# circuitcop.net
KiCad netlist of a schematic drawn in EAGLE
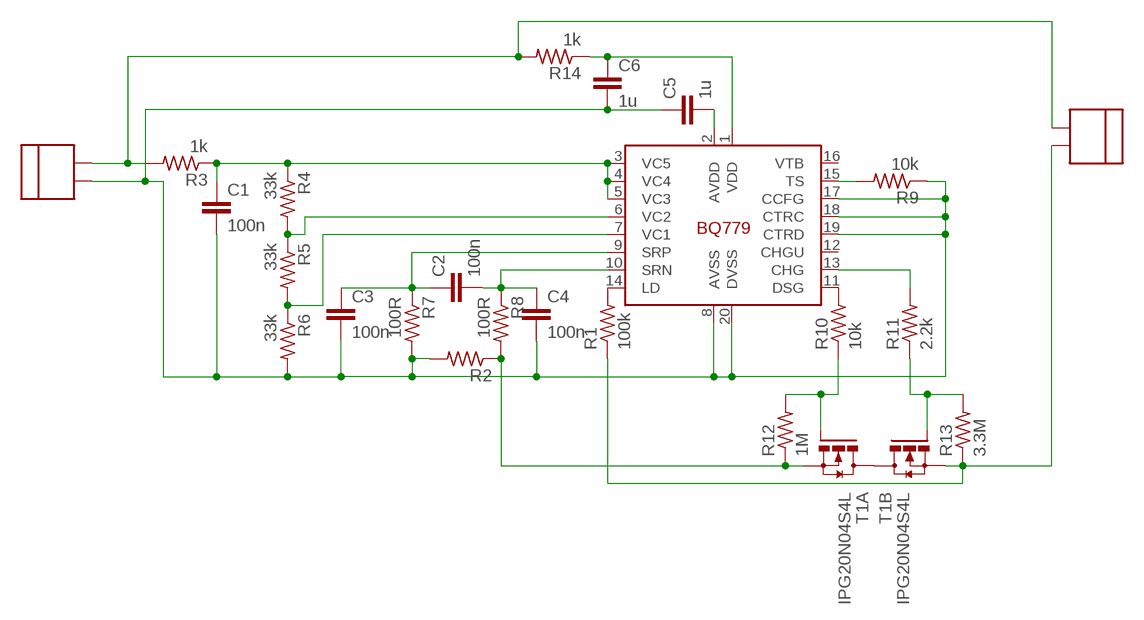
[diagram p0: schematic, sheet 1]

(export (version "E")
  (design (tool "Eeschema 10.0.6"))
  (components
    (comp (ref "C1")
      (value "100n")
      (footprint "eagle-import:C0805")
      (libsource (lib "eagle-import") (part "C-EUC0805"))
    )
    (comp (ref "C2")
      (value "100n")
      (footprint "eagle-import:C0805")
      (libsource (lib "eagle-import") (part "C-EUC0805"))
    )
    (comp (ref "C3")
      (value "100n")
      (footprint "eagle-import:C0805")
      (libsource (lib "eagle-import") (part "C-EUC0805"))
    )
    (comp (ref "C4")
      (value "100n")
      (footprint "eagle-import:C0805")
      (libsource (lib "eagle-import") (part "C-EUC0805"))
    )
    (comp (ref "C5")
      (value "1u")
      (footprint "eagle-import:C0805")
      (libsource (lib "eagle-import") (part "C-EUC0805"))
    )
    (comp (ref "C6")
      (value "1u")
      (footprint "eagle-import:C0805")
      (libsource (lib "eagle-import") (part "C-EUC0805"))
    )
    (comp (ref "R1")
      (value "100k")
      (footprint "eagle-import:R0805")
      (libsource (lib "eagle-import") (part "R-US_R0805"))
    )
    (comp (ref "R2")
      (value "R-US_R1206")
      (footprint "eagle-import:R1206")
      (libsource (lib "eagle-import") (part "R-US_R1206"))
    )
    (comp (ref "R3")
      (value "1k")
      (footprint "eagle-import:R0805")
      (libsource (lib "eagle-import") (part "R-US_R0805"))
    )
    (comp (ref "R4")
      (value "33k")
      (footprint "eagle-import:R0805")
      (libsource (lib "eagle-import") (part "R-US_R0805"))
    )
    (comp (ref "R5")
      (value "33k")
      (footprint "eagle-import:R0805")
      (libsource (lib "eagle-import") (part "R-US_R0805"))
    )
    (comp (ref "R6")
      (value "33k")
      (footprint "eagle-import:R0805")
      (libsource (lib "eagle-import") (part "R-US_R0805"))
    )
    (comp (ref "R7")
      (value "100R")
      (footprint "eagle-import:R0805")
      (libsource (lib "eagle-import") (part "R-US_R0805"))
    )
    (comp (ref "R8")
      (value "100R")
      (footprint "eagle-import:R0805")
      (libsource (lib "eagle-import") (part "R-US_R0805"))
    )
    (comp (ref "R9")
      (value "10k")
      (footprint "eagle-import:R0805")
      (libsource (lib "eagle-import") (part "R-US_R0805"))
    )
    (comp (ref "R10")
      (value "10k")
      (footprint "eagle-import:R0805")
      (libsource (lib "eagle-import") (part "R-US_R0805"))
    )
    (comp (ref "R11")
      (value "2.2k")
      (footprint "eagle-import:R0805")
      (libsource (lib "eagle-import") (part "R-US_R0805"))
    )
    (comp (ref "R12")
      (value "1M")
      (footprint "eagle-import:R0805")
      (libsource (lib "eagle-import") (part "R-US_R0805"))
    )
    (comp (ref "R13")
      (value "3.3M")
      (footprint "eagle-import:R0805")
      (libsource (lib "eagle-import") (part "R-US_R0805"))
    )
    (comp (ref "R14")
      (value "1k")
      (footprint "eagle-import:R0805")
      (libsource (lib "eagle-import") (part "R-US_R0805"))
    )
    (comp (ref "T1")
      (value "IPG20N04S4L")
      (footprint "eagle-import:PG-TDSON-8")
      (libsource (lib "eagle-import") (part "IPG20N04S4L"))
    )
    (comp (ref "U$1")
      (value "CTB5202/2")
      (footprint "eagle-import:CTB5202_2")
      (libsource (lib "eagle-import") (part "CTB5202/2"))
    )
    (comp (ref "U$2")
      (value "CTB5202/2")
      (footprint "eagle-import:CTB5202_2")
      (libsource (lib "eagle-import") (part "CTB5202/2"))
    )
    (comp (ref "U1")
      (value "BQ779")
      (footprint "eagle-import:TSSOP20")
      (libsource (lib "eagle-import") (part "BQ779"))
    )
  )
  (nets
    (net (code "1") (name "Net-(T1A-D-Pad7)") (class "Default")
      (node (ref "T1") (pin "5") (pinfunction "D_5") (pintype "passive"))
      (node (ref "T1") (pin "6") (pinfunction "D_6") (pintype "passive"))
      (node (ref "T1") (pin "7") (pinfunction "D_7") (pintype "passive"))
      (node (ref "T1") (pin "8") (pinfunction "D_8") (pintype "passive"))
      (node (ref "T1") (pin "TH1") (pinfunction "D_TH1") (pintype "passive"))
      (node (ref "T1") (pin "TH2") (pinfunction "D_TH2") (pintype "passive"))
    )
    (net (code "2") (name "Net-(T1A-G)") (class "Default")
      (node (ref "R10") (pin "1") (pinfunction "1_1") (pintype "passive"))
      (node (ref "R12") (pin "2") (pinfunction "2_2") (pintype "passive"))
      (node (ref "T1") (pin "2") (pinfunction "G_2") (pintype "passive"))
    )
    (net (code "3") (name "Net-(T1A-S)") (class "Default")
      (node (ref "R12") (pin "1") (pinfunction "1_1") (pintype "passive"))
      (node (ref "R2") (pin "1") (pinfunction "1_1") (pintype "passive"))
      (node (ref "R8") (pin "2") (pinfunction "2_2") (pintype "passive"))
      (node (ref "T1") (pin "1") (pinfunction "S_1") (pintype "passive"))
    )
    (net (code "4") (name "Net-(T1B-G)") (class "Default")
      (node (ref "R11") (pin "1") (pinfunction "1_1") (pintype "passive"))
      (node (ref "R13") (pin "2") (pinfunction "2_2") (pintype "passive"))
      (node (ref "T1") (pin "4") (pinfunction "G_4") (pintype "passive"))
    )
    (net (code "5") (name "Net-(T1B-S)") (class "Default")
      (node (ref "R1") (pin "1") (pinfunction "1_1") (pintype "passive"))
      (node (ref "R13") (pin "1") (pinfunction "1_1") (pintype "passive"))
      (node (ref "T1") (pin "3") (pinfunction "S_3") (pintype "passive"))
      (node (ref "U$2") (pin "P$2") (pinfunction "2_P$2") (pintype "bidirectional"))
    )
    (net (code "6") (name "Net-(U$1-1)") (class "Default")
      (node (ref "C1") (pin "2") (pinfunction "2_2") (pintype "passive"))
      (node (ref "C3") (pin "2") (pinfunction "2_2") (pintype "passive"))
      (node (ref "C4") (pin "2") (pinfunction "2_2") (pintype "passive"))
      (node (ref "C5") (pin "1") (pinfunction "1_1") (pintype "passive"))
      (node (ref "C6") (pin "2") (pinfunction "2_2") (pintype "passive"))
      (node (ref "R2") (pin "2") (pinfunction "2_2") (pintype "passive"))
      (node (ref "R6") (pin "2") (pinfunction "2_2") (pintype "passive"))
      (node (ref "R7") (pin "2") (pinfunction "2_2") (pintype "passive"))
      (node (ref "R9") (pin "1") (pinfunction "1_1") (pintype "passive"))
      (node (ref "U$1") (pin "P$1") (pinfunction "1_P$1") (pintype "bidirectional"))
      (node (ref "U1") (pin "17") (pinfunction "CCFG_17") (pintype "input"))
      (node (ref "U1") (pin "18") (pinfunction "CTRC_18") (pintype "input"))
      (node (ref "U1") (pin "19") (pinfunction "CTRD_19") (pintype "input"))
      (node (ref "U1") (pin "20") (pinfunction "DVSS_20") (pintype "power_in"))
      (node (ref "U1") (pin "8") (pinfunction "AVSS_8") (pintype "power_in"))
    )
    (net (code "7") (name "Net-(U$1-2)") (class "Default")
      (node (ref "R14") (pin "2") (pinfunction "2_2") (pintype "passive"))
      (node (ref "R3") (pin "2") (pinfunction "2_2") (pintype "passive"))
      (node (ref "U$1") (pin "P$2") (pinfunction "2_P$2") (pintype "bidirectional"))
      (node (ref "U$2") (pin "P$1") (pinfunction "1_P$1") (pintype "bidirectional"))
    )
    (net (code "8") (name "Net-(U1-AVDD)") (class "Default")
      (node (ref "C5") (pin "2") (pinfunction "2_2") (pintype "passive"))
      (node (ref "U1") (pin "2") (pinfunction "AVDD_2") (pintype "power_in"))
    )
    (net (code "9") (name "Net-(U1-CHG)") (class "Default")
      (node (ref "R11") (pin "2") (pinfunction "2_2") (pintype "passive"))
      (node (ref "U1") (pin "13") (pinfunction "CHG_13") (pintype "output"))
    )
    (net (code "10") (name "Net-(U1-DSG)") (class "Default")
      (node (ref "R10") (pin "2") (pinfunction "2_2") (pintype "passive"))
      (node (ref "U1") (pin "11") (pinfunction "DSG_11") (pintype "output"))
    )
    (net (code "11") (name "Net-(U1-LD)") (class "Default")
      (node (ref "R1") (pin "2") (pinfunction "2_2") (pintype "passive"))
      (node (ref "U1") (pin "14") (pinfunction "LD_14") (pintype "input"))
    )
    (net (code "12") (name "Net-(U1-SRN)") (class "Default")
      (node (ref "C2") (pin "2") (pinfunction "2_2") (pintype "passive"))
      (node (ref "C4") (pin "1") (pinfunction "1_1") (pintype "passive"))
      (node (ref "R8") (pin "1") (pinfunction "1_1") (pintype "passive"))
      (node (ref "U1") (pin "10") (pinfunction "SRN_10") (pintype "input"))
    )
    (net (code "13") (name "Net-(U1-SRP)") (class "Default")
      (node (ref "C2") (pin "1") (pinfunction "1_1") (pintype "passive"))
      (node (ref "C3") (pin "1") (pinfunction "1_1") (pintype "passive"))
      (node (ref "R7") (pin "1") (pinfunction "1_1") (pintype "passive"))
      (node (ref "U1") (pin "9") (pinfunction "SRP_9") (pintype "input"))
    )
    (net (code "14") (name "Net-(U1-TS)") (class "Default")
      (node (ref "R9") (pin "2") (pinfunction "2_2") (pintype "passive"))
      (node (ref "U1") (pin "15") (pinfunction "TS_15") (pintype "input"))
    )
    (net (code "15") (name "Net-(U1-VC1)") (class "Default")
      (node (ref "R5") (pin "2") (pinfunction "2_2") (pintype "passive"))
      (node (ref "R6") (pin "1") (pinfunction "1_1") (pintype "passive"))
      (node (ref "U1") (pin "7") (pinfunction "VC1_7") (pintype "input"))
    )
    (net (code "16") (name "Net-(U1-VC2)") (class "Default")
      (node (ref "R4") (pin "2") (pinfunction "2_2") (pintype "passive"))
      (node (ref "R5") (pin "1") (pinfunction "1_1") (pintype "passive"))
      (node (ref "U1") (pin "6") (pinfunction "VC2_6") (pintype "input"))
    )
    (net (code "17") (name "Net-(U1-VC3)") (class "Default")
      (node (ref "C1") (pin "1") (pinfunction "1_1") (pintype "passive"))
      (node (ref "R3") (pin "1") (pinfunction "1_1") (pintype "passive"))
      (node (ref "R4") (pin "1") (pinfunction "1_1") (pintype "passive"))
      (node (ref "U1") (pin "3") (pinfunction "VC5_3") (pintype "input"))
      (node (ref "U1") (pin "4") (pinfunction "VC4_4") (pintype "input"))
      (node (ref "U1") (pin "5") (pinfunction "VC3_5") (pintype "input"))
    )
    (net (code "18") (name "Net-(U1-VDD)") (class "Default")
      (node (ref "C6") (pin "1") (pinfunction "1_1") (pintype "passive"))
      (node (ref "R14") (pin "1") (pinfunction "1_1") (pintype "passive"))
      (node (ref "U1") (pin "1") (pinfunction "VDD_1") (pintype "power_in"))
    )
    (net (code "19") (name "unconnected-(U1-CHGU-Pad12)") (class "Default")
      (node (ref "U1") (pin "12") (pinfunction "CHGU_12") (pintype "output"))
    )
    (net (code "20") (name "unconnected-(U1-VTB-Pad16)") (class "Default")
      (node (ref "U1") (pin "16") (pinfunction "VTB_16") (pintype "output"))
    )
  )
)
